# Cart64out.net
KiCad netlist of a schematic drawn in EAGLE
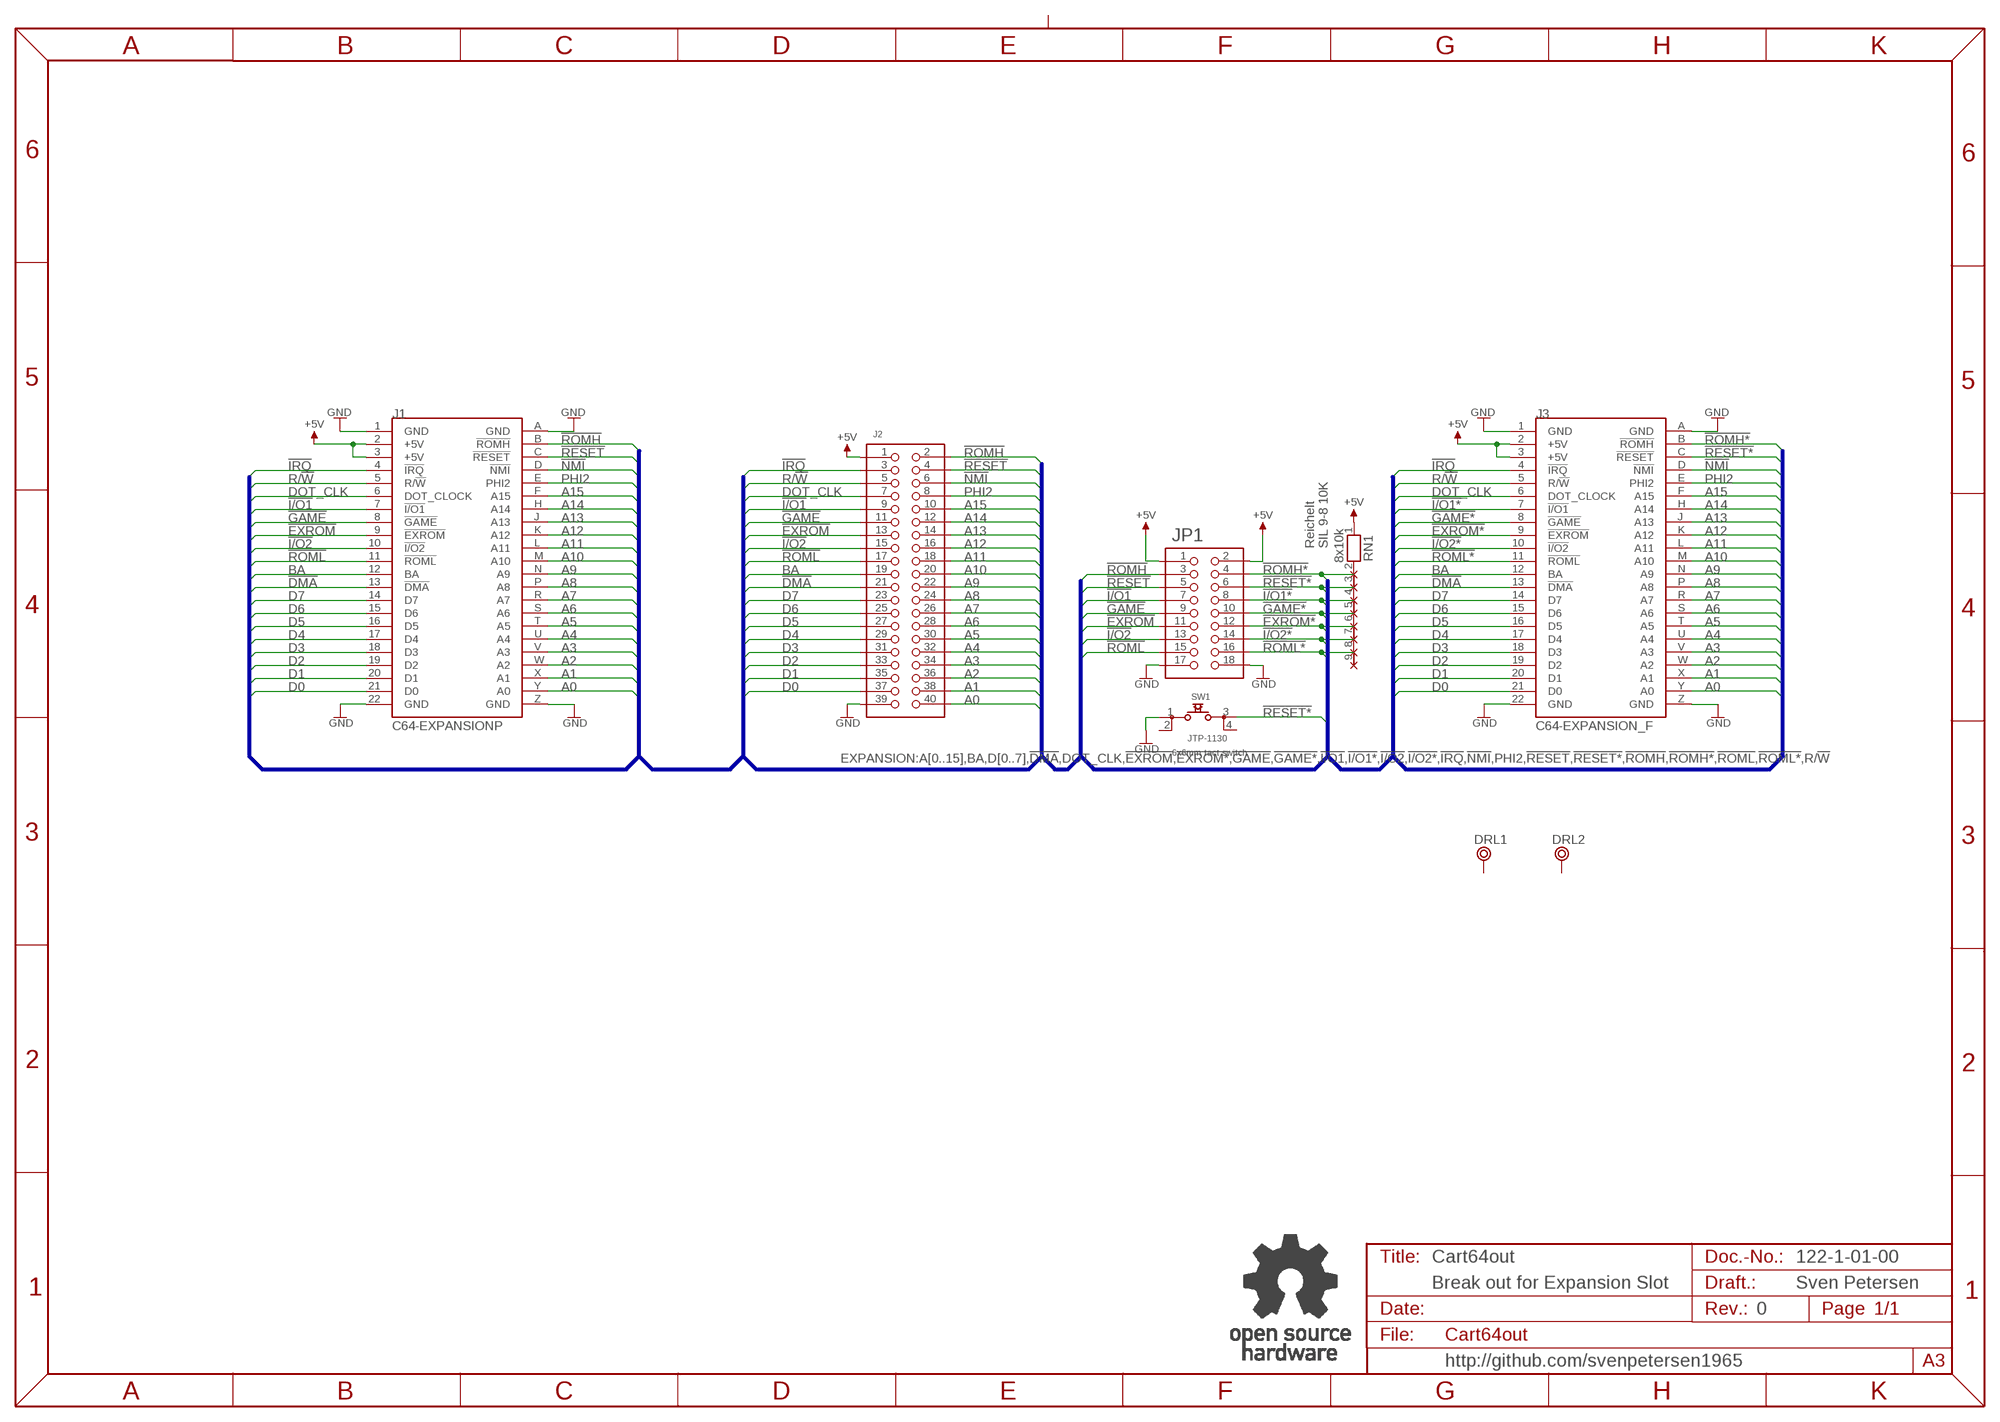
[diagram p0: schematic, sheet 1]

(export (version "E")
  (design (tool "Eeschema 10.0.6"))
  (components
    (comp (ref "DRL1")
      (value "BOHR3,3")
      (footprint "eagle-import:BOHR3,3")
      (libsource (lib "eagle-import") (part "BOHR3,3"))
    )
    (comp (ref "DRL2")
      (value "BOHR3,3")
      (footprint "eagle-import:BOHR3,3")
      (libsource (lib "eagle-import") (part "BOHR3,3"))
    )
    (comp (ref "J1")
      (value "C64-EXPANSIONP")
      (footprint "eagle-import:EXPPORT")
      (libsource (lib "eagle-import") (part "C64-EXPANSIONP"))
    )
    (comp (ref "J2")
      (value "PINHD-2X20WV")
      (footprint "eagle-import:2X20WV")
      (libsource (lib "eagle-import") (part "PINHD-2X20WV"))
    )
    (comp (ref "J3")
      (value "C64-EXPANSION_F")
      (footprint "eagle-import:EXPANSION_OUT")
      (libsource (lib "eagle-import") (part "C64-EXPANSION_F"))
    )
    (comp (ref "JP1")
      (value "PINHD-2X9")
      (footprint "eagle-import:2X09")
      (libsource (lib "eagle-import") (part "PINHD-2X9"))
    )
    (comp (ref "RN1")
      (value "8x10k")
      (footprint "eagle-import:RN-9")
      (libsource (lib "eagle-import") (part "RN08"))
    )
    (comp (ref "SW1")
      (value "JTP-1130")
      (footprint "eagle-import:JTP-1130")
      (libsource (lib "eagle-import") (part "JTP-1130"))
    )
    (comp (ref "U$22")
      (value "OPEN_SOURCE_HW")
      (footprint "eagle-import:OPENHW")
      (libsource (lib "eagle-import") (part "OPEN_SOURCE_HW"))
    )
  )
  (nets
    (net (code "1") (name "+5V") (class "Default")
      (node (ref "J1") (pin "2") (pinfunction "+5V_2") (pintype "power_in"))
      (node (ref "J1") (pin "3") (pinfunction "+5V_3") (pintype "power_in"))
      (node (ref "J2") (pin "1") (pinfunction "1_1") (pintype "passive"))
      (node (ref "J3") (pin "2") (pinfunction "+5V_2") (pintype "power_in"))
      (node (ref "J3") (pin "3") (pinfunction "+5V_3") (pintype "power_in"))
      (node (ref "JP1") (pin "1") (pinfunction "1_1") (pintype "passive"))
      (node (ref "JP1") (pin "2") (pinfunction "2_2") (pintype "passive"))
      (node (ref "RN1") (pin "1") (pinfunction "1_1") (pintype "passive"))
    )
    (net (code "2") (name "/A0") (class "Default")
      (node (ref "J1") (pin "Y") (pinfunction "A0_Y") (pintype "bidirectional"))
      (node (ref "J2") (pin "40") (pinfunction "40_40") (pintype "passive"))
      (node (ref "J3") (pin "Y") (pinfunction "A0_Y") (pintype "bidirectional"))
    )
    (net (code "3") (name "/A1") (class "Default")
      (node (ref "J1") (pin "X") (pinfunction "A1_X") (pintype "bidirectional"))
      (node (ref "J2") (pin "38") (pinfunction "38_38") (pintype "passive"))
      (node (ref "J3") (pin "X") (pinfunction "A1_X") (pintype "bidirectional"))
    )
    (net (code "4") (name "/A2") (class "Default")
      (node (ref "J1") (pin "W") (pinfunction "A2_W") (pintype "bidirectional"))
      (node (ref "J2") (pin "36") (pinfunction "36_36") (pintype "passive"))
      (node (ref "J3") (pin "W") (pinfunction "A2_W") (pintype "bidirectional"))
    )
    (net (code "5") (name "/A3") (class "Default")
      (node (ref "J1") (pin "V") (pinfunction "A3_V") (pintype "bidirectional"))
      (node (ref "J2") (pin "34") (pinfunction "34_34") (pintype "passive"))
      (node (ref "J3") (pin "V") (pinfunction "A3_V") (pintype "bidirectional"))
    )
    (net (code "6") (name "/A4") (class "Default")
      (node (ref "J1") (pin "U") (pinfunction "A4_U") (pintype "bidirectional"))
      (node (ref "J2") (pin "32") (pinfunction "32_32") (pintype "passive"))
      (node (ref "J3") (pin "U") (pinfunction "A4_U") (pintype "bidirectional"))
    )
    (net (code "7") (name "/A5") (class "Default")
      (node (ref "J1") (pin "T") (pinfunction "A5_T") (pintype "bidirectional"))
      (node (ref "J2") (pin "30") (pinfunction "30_30") (pintype "passive"))
      (node (ref "J3") (pin "T") (pinfunction "A5_T") (pintype "bidirectional"))
    )
    (net (code "8") (name "/A6") (class "Default")
      (node (ref "J1") (pin "S") (pinfunction "A6_S") (pintype "bidirectional"))
      (node (ref "J2") (pin "28") (pinfunction "28_28") (pintype "passive"))
      (node (ref "J3") (pin "S") (pinfunction "A6_S") (pintype "bidirectional"))
    )
    (net (code "9") (name "/A7") (class "Default")
      (node (ref "J1") (pin "R") (pinfunction "A7_R") (pintype "bidirectional"))
      (node (ref "J2") (pin "26") (pinfunction "26_26") (pintype "passive"))
      (node (ref "J3") (pin "R") (pinfunction "A7_R") (pintype "bidirectional"))
    )
    (net (code "10") (name "/A8") (class "Default")
      (node (ref "J1") (pin "P") (pinfunction "A8_P") (pintype "bidirectional"))
      (node (ref "J2") (pin "24") (pinfunction "24_24") (pintype "passive"))
      (node (ref "J3") (pin "P") (pinfunction "A8_P") (pintype "bidirectional"))
    )
    (net (code "11") (name "/A9") (class "Default")
      (node (ref "J1") (pin "N") (pinfunction "A9_N") (pintype "bidirectional"))
      (node (ref "J2") (pin "22") (pinfunction "22_22") (pintype "passive"))
      (node (ref "J3") (pin "N") (pinfunction "A9_N") (pintype "bidirectional"))
    )
    (net (code "12") (name "/A10") (class "Default")
      (node (ref "J1") (pin "M") (pinfunction "A10_M") (pintype "bidirectional"))
      (node (ref "J2") (pin "20") (pinfunction "20_20") (pintype "passive"))
      (node (ref "J3") (pin "M") (pinfunction "A10_M") (pintype "bidirectional"))
    )
    (net (code "13") (name "/A11") (class "Default")
      (node (ref "J1") (pin "L") (pinfunction "A11_L") (pintype "bidirectional"))
      (node (ref "J2") (pin "18") (pinfunction "18_18") (pintype "passive"))
      (node (ref "J3") (pin "L") (pinfunction "A11_L") (pintype "bidirectional"))
    )
    (net (code "14") (name "/A12") (class "Default")
      (node (ref "J1") (pin "K") (pinfunction "A12_K") (pintype "bidirectional"))
      (node (ref "J2") (pin "16") (pinfunction "16_16") (pintype "passive"))
      (node (ref "J3") (pin "K") (pinfunction "A12_K") (pintype "bidirectional"))
    )
    (net (code "15") (name "/A13") (class "Default")
      (node (ref "J1") (pin "J") (pinfunction "A13_J") (pintype "bidirectional"))
      (node (ref "J2") (pin "14") (pinfunction "14_14") (pintype "passive"))
      (node (ref "J3") (pin "J") (pinfunction "A13_J") (pintype "bidirectional"))
    )
    (net (code "16") (name "/A14") (class "Default")
      (node (ref "J1") (pin "H") (pinfunction "A14_H") (pintype "bidirectional"))
      (node (ref "J2") (pin "12") (pinfunction "12_12") (pintype "passive"))
      (node (ref "J3") (pin "H") (pinfunction "A14_H") (pintype "bidirectional"))
    )
    (net (code "17") (name "/A15") (class "Default")
      (node (ref "J1") (pin "F") (pinfunction "A15_F") (pintype "bidirectional"))
      (node (ref "J2") (pin "10") (pinfunction "10_10") (pintype "passive"))
      (node (ref "J3") (pin "F") (pinfunction "A15_F") (pintype "bidirectional"))
    )
    (net (code "18") (name "/BA") (class "Default")
      (node (ref "J1") (pin "12") (pinfunction "BA_12") (pintype "output"))
      (node (ref "J2") (pin "19") (pinfunction "19_19") (pintype "passive"))
      (node (ref "J3") (pin "12") (pinfunction "BA_12") (pintype "output"))
    )
    (net (code "19") (name "/D0") (class "Default")
      (node (ref "J1") (pin "21") (pinfunction "D0_21") (pintype "bidirectional"))
      (node (ref "J2") (pin "37") (pinfunction "37_37") (pintype "passive"))
      (node (ref "J3") (pin "21") (pinfunction "D0_21") (pintype "bidirectional"))
    )
    (net (code "20") (name "/D1") (class "Default")
      (node (ref "J1") (pin "20") (pinfunction "D1_20") (pintype "bidirectional"))
      (node (ref "J2") (pin "35") (pinfunction "35_35") (pintype "passive"))
      (node (ref "J3") (pin "20") (pinfunction "D1_20") (pintype "bidirectional"))
    )
    (net (code "21") (name "/D2") (class "Default")
      (node (ref "J1") (pin "19") (pinfunction "D2_19") (pintype "bidirectional"))
      (node (ref "J2") (pin "33") (pinfunction "33_33") (pintype "passive"))
      (node (ref "J3") (pin "19") (pinfunction "D2_19") (pintype "bidirectional"))
    )
    (net (code "22") (name "/D3") (class "Default")
      (node (ref "J1") (pin "18") (pinfunction "D3_18") (pintype "bidirectional"))
      (node (ref "J2") (pin "31") (pinfunction "31_31") (pintype "passive"))
      (node (ref "J3") (pin "18") (pinfunction "D3_18") (pintype "bidirectional"))
    )
    (net (code "23") (name "/D4") (class "Default")
      (node (ref "J1") (pin "17") (pinfunction "D4_17") (pintype "bidirectional"))
      (node (ref "J2") (pin "29") (pinfunction "29_29") (pintype "passive"))
      (node (ref "J3") (pin "17") (pinfunction "D4_17") (pintype "bidirectional"))
    )
    (net (code "24") (name "/D5") (class "Default")
      (node (ref "J1") (pin "16") (pinfunction "D5_16") (pintype "bidirectional"))
      (node (ref "J2") (pin "27") (pinfunction "27_27") (pintype "passive"))
      (node (ref "J3") (pin "16") (pinfunction "D5_16") (pintype "bidirectional"))
    )
    (net (code "25") (name "/D6") (class "Default")
      (node (ref "J1") (pin "15") (pinfunction "D6_15") (pintype "bidirectional"))
      (node (ref "J2") (pin "25") (pinfunction "25_25") (pintype "passive"))
      (node (ref "J3") (pin "15") (pinfunction "D6_15") (pintype "bidirectional"))
    )
    (net (code "26") (name "/D7") (class "Default")
      (node (ref "J1") (pin "14") (pinfunction "D7_14") (pintype "bidirectional"))
      (node (ref "J2") (pin "23") (pinfunction "23_23") (pintype "passive"))
      (node (ref "J3") (pin "14") (pinfunction "D7_14") (pintype "bidirectional"))
    )
    (net (code "27") (name "/DOT_CLK") (class "Default")
      (node (ref "J1") (pin "6") (pinfunction "DOT_CLOCK_6") (pintype "output"))
      (node (ref "J2") (pin "7") (pinfunction "7_7") (pintype "passive"))
      (node (ref "J3") (pin "6") (pinfunction "DOT_CLOCK_6") (pintype "output"))
    )
    (net (code "28") (name "/PHI2") (class "Default")
      (node (ref "J1") (pin "E") (pinfunction "PHI2_E") (pintype "output"))
      (node (ref "J2") (pin "8") (pinfunction "8_8") (pintype "passive"))
      (node (ref "J3") (pin "E") (pinfunction "PHI2_E") (pintype "output"))
    )
    (net (code "29") (name "/R{slash}~{W}") (class "Default")
      (node (ref "J1") (pin "5") (pinfunction "R/~{W}_5") (pintype "output"))
      (node (ref "J2") (pin "5") (pinfunction "5_5") (pintype "passive"))
      (node (ref "J3") (pin "5") (pinfunction "R/~{W}_5") (pintype "output"))
    )
    (net (code "31") (name "/~{DMA}") (class "Default")
      (node (ref "J1") (pin "13") (pinfunction "~{DMA}_13") (pintype "input"))
      (node (ref "J2") (pin "21") (pinfunction "21_21") (pintype "passive"))
      (node (ref "J3") (pin "13") (pinfunction "~{DMA}_13") (pintype "input"))
    )
    (net (code "32") (name "/~{EXROM*}") (class "Default")
      (node (ref "J3") (pin "9") (pinfunction "~{EXROM}_9") (pintype "input"))
      (node (ref "JP1") (pin "12") (pinfunction "12_12") (pintype "passive"))
      (node (ref "RN1") (pin "6") (pinfunction "6_6") (pintype "passive"))
    )
    (net (code "33") (name "/~{EXROM}") (class "Default")
      (node (ref "J1") (pin "9") (pinfunction "~{EXROM}_9") (pintype "input"))
      (node (ref "J2") (pin "13") (pinfunction "13_13") (pintype "passive"))
      (node (ref "JP1") (pin "11") (pinfunction "11_11") (pintype "passive"))
    )
    (net (code "34") (name "/~{GAME*}") (class "Default")
      (node (ref "J3") (pin "8") (pinfunction "~{GAME}_8") (pintype "input"))
      (node (ref "JP1") (pin "10") (pinfunction "10_10") (pintype "passive"))
      (node (ref "RN1") (pin "5") (pinfunction "5_5") (pintype "passive"))
    )
    (net (code "35") (name "/~{GAME}") (class "Default")
      (node (ref "J1") (pin "8") (pinfunction "~{GAME}_8") (pintype "input"))
      (node (ref "J2") (pin "11") (pinfunction "11_11") (pintype "passive"))
      (node (ref "JP1") (pin "9") (pinfunction "9_9") (pintype "passive"))
    )
    (net (code "36") (name "/~{IRQ}") (class "Default")
      (node (ref "J1") (pin "4") (pinfunction "~{IRQ}_4") (pintype "input"))
      (node (ref "J2") (pin "3") (pinfunction "3_3") (pintype "passive"))
      (node (ref "J3") (pin "4") (pinfunction "~{IRQ}_4") (pintype "input"))
    )
    (net (code "37") (name "/~{I{slash}O1*}") (class "Default")
      (node (ref "J3") (pin "7") (pinfunction "~{I/O1}_7") (pintype "output"))
      (node (ref "JP1") (pin "8") (pinfunction "8_8") (pintype "passive"))
      (node (ref "RN1") (pin "4") (pinfunction "4_4") (pintype "passive"))
    )
    (net (code "38") (name "/~{I{slash}O1}") (class "Default")
      (node (ref "J1") (pin "7") (pinfunction "~{I/O1}_7") (pintype "output"))
      (node (ref "J2") (pin "9") (pinfunction "9_9") (pintype "passive"))
      (node (ref "JP1") (pin "7") (pinfunction "7_7") (pintype "passive"))
    )
    (net (code "39") (name "/~{I{slash}O2*}") (class "Default")
      (node (ref "J3") (pin "10") (pinfunction "~{I/O2}_10") (pintype "output"))
      (node (ref "JP1") (pin "14") (pinfunction "14_14") (pintype "passive"))
      (node (ref "RN1") (pin "7") (pinfunction "7_7") (pintype "passive"))
    )
    (net (code "40") (name "/~{I{slash}O2}") (class "Default")
      (node (ref "J1") (pin "10") (pinfunction "~{I/O2}_10") (pintype "output"))
      (node (ref "J2") (pin "15") (pinfunction "15_15") (pintype "passive"))
      (node (ref "JP1") (pin "13") (pinfunction "13_13") (pintype "passive"))
    )
    (net (code "41") (name "/~{NMI}") (class "Default")
      (node (ref "J1") (pin "D") (pinfunction "~{NMI}_D") (pintype "input"))
      (node (ref "J2") (pin "6") (pinfunction "6_6") (pintype "passive"))
      (node (ref "J3") (pin "D") (pinfunction "~{NMI}_D") (pintype "input"))
    )
    (net (code "42") (name "/~{RESET*}") (class "Default")
      (node (ref "J3") (pin "C") (pinfunction "~{RESET}_C") (pintype "open_collector"))
      (node (ref "JP1") (pin "6") (pinfunction "6_6") (pintype "passive"))
      (node (ref "RN1") (pin "3") (pinfunction "3_3") (pintype "passive"))
      (node (ref "SW1") (pin "3") (pinfunction "3_3") (pintype "passive"))
    )
    (net (code "43") (name "/~{RESET}") (class "Default")
      (node (ref "J1") (pin "C") (pinfunction "~{RESET}_C") (pintype "open_collector"))
      (node (ref "J2") (pin "4") (pinfunction "4_4") (pintype "passive"))
      (node (ref "JP1") (pin "5") (pinfunction "5_5") (pintype "passive"))
    )
    (net (code "44") (name "/~{ROMH*}") (class "Default")
      (node (ref "J3") (pin "B") (pinfunction "~{ROMH}_B") (pintype "output"))
      (node (ref "JP1") (pin "4") (pinfunction "4_4") (pintype "passive"))
      (node (ref "RN1") (pin "2") (pinfunction "2_2") (pintype "passive"))
    )
    (net (code "45") (name "/~{ROMH}") (class "Default")
      (node (ref "J1") (pin "B") (pinfunction "~{ROMH}_B") (pintype "output"))
      (node (ref "J2") (pin "2") (pinfunction "2_2") (pintype "passive"))
      (node (ref "JP1") (pin "3") (pinfunction "3_3") (pintype "passive"))
    )
    (net (code "46") (name "/~{ROML*}") (class "Default")
      (node (ref "J3") (pin "11") (pinfunction "~{ROML}_11") (pintype "output"))
      (node (ref "JP1") (pin "16") (pinfunction "16_16") (pintype "passive"))
      (node (ref "RN1") (pin "8") (pinfunction "8_8") (pintype "passive"))
    )
    (net (code "47") (name "/~{ROML}") (class "Default")
      (node (ref "J1") (pin "11") (pinfunction "~{ROML}_11") (pintype "output"))
      (node (ref "J2") (pin "17") (pinfunction "17_17") (pintype "passive"))
      (node (ref "JP1") (pin "15") (pinfunction "15_15") (pintype "passive"))
    )
    (net (code "48") (name "GND") (class "Default")
      (node (ref "J1") (pin "1") (pinfunction "GND_1") (pintype "power_in"))
      (node (ref "J1") (pin "22") (pinfunction "GND_22") (pintype "power_in"))
      (node (ref "J1") (pin "A") (pinfunction "GND_A") (pintype "power_in"))
      (node (ref "J1") (pin "Z") (pinfunction "GND_Z") (pintype "power_in"))
      (node (ref "J2") (pin "39") (pinfunction "39_39") (pintype "passive"))
      (node (ref "J3") (pin "1") (pinfunction "GND_1") (pintype "power_in"))
      (node (ref "J3") (pin "22") (pinfunction "GND_22") (pintype "power_in"))
      (node (ref "J3") (pin "A") (pinfunction "GND_A") (pintype "power_in"))
      (node (ref "J3") (pin "Z") (pinfunction "GND_Z") (pintype "power_in"))
      (node (ref "JP1") (pin "17") (pinfunction "17_17") (pintype "passive"))
      (node (ref "JP1") (pin "18") (pinfunction "18_18") (pintype "passive"))
      (node (ref "SW1") (pin "1") (pinfunction "1_1") (pintype "passive"))
    )
    (net (code "49") (name "unconnected-(DRL1-PadP$1)") (class "Default")
      (node (ref "DRL1") (pin "P$1") (pinfunction "P$1_P$1") (pintype "passive"))
    )
    (net (code "50") (name "unconnected-(DRL2-PadP$1)") (class "Default")
      (node (ref "DRL2") (pin "P$1") (pinfunction "P$1_P$1") (pintype "passive"))
    )
    (net (code "51") (name "unconnected-(RN1-Pad9)") (class "Default")
      (node (ref "RN1") (pin "9") (pinfunction "9_9") (pintype "passive"))
    )
    (net (code "52") (name "unconnected-(SW1-Pad2)") (class "Default")
      (node (ref "SW1") (pin "2") (pinfunction "2_2") (pintype "passive"))
    )
    (net (code "53") (name "unconnected-(SW1-Pad4)") (class "Default")
      (node (ref "SW1") (pin "4") (pinfunction "4_4") (pintype "passive"))
    )
  )
)
